# flashlightswitchv02.net
KiCad netlist of a schematic drawn in EAGLE
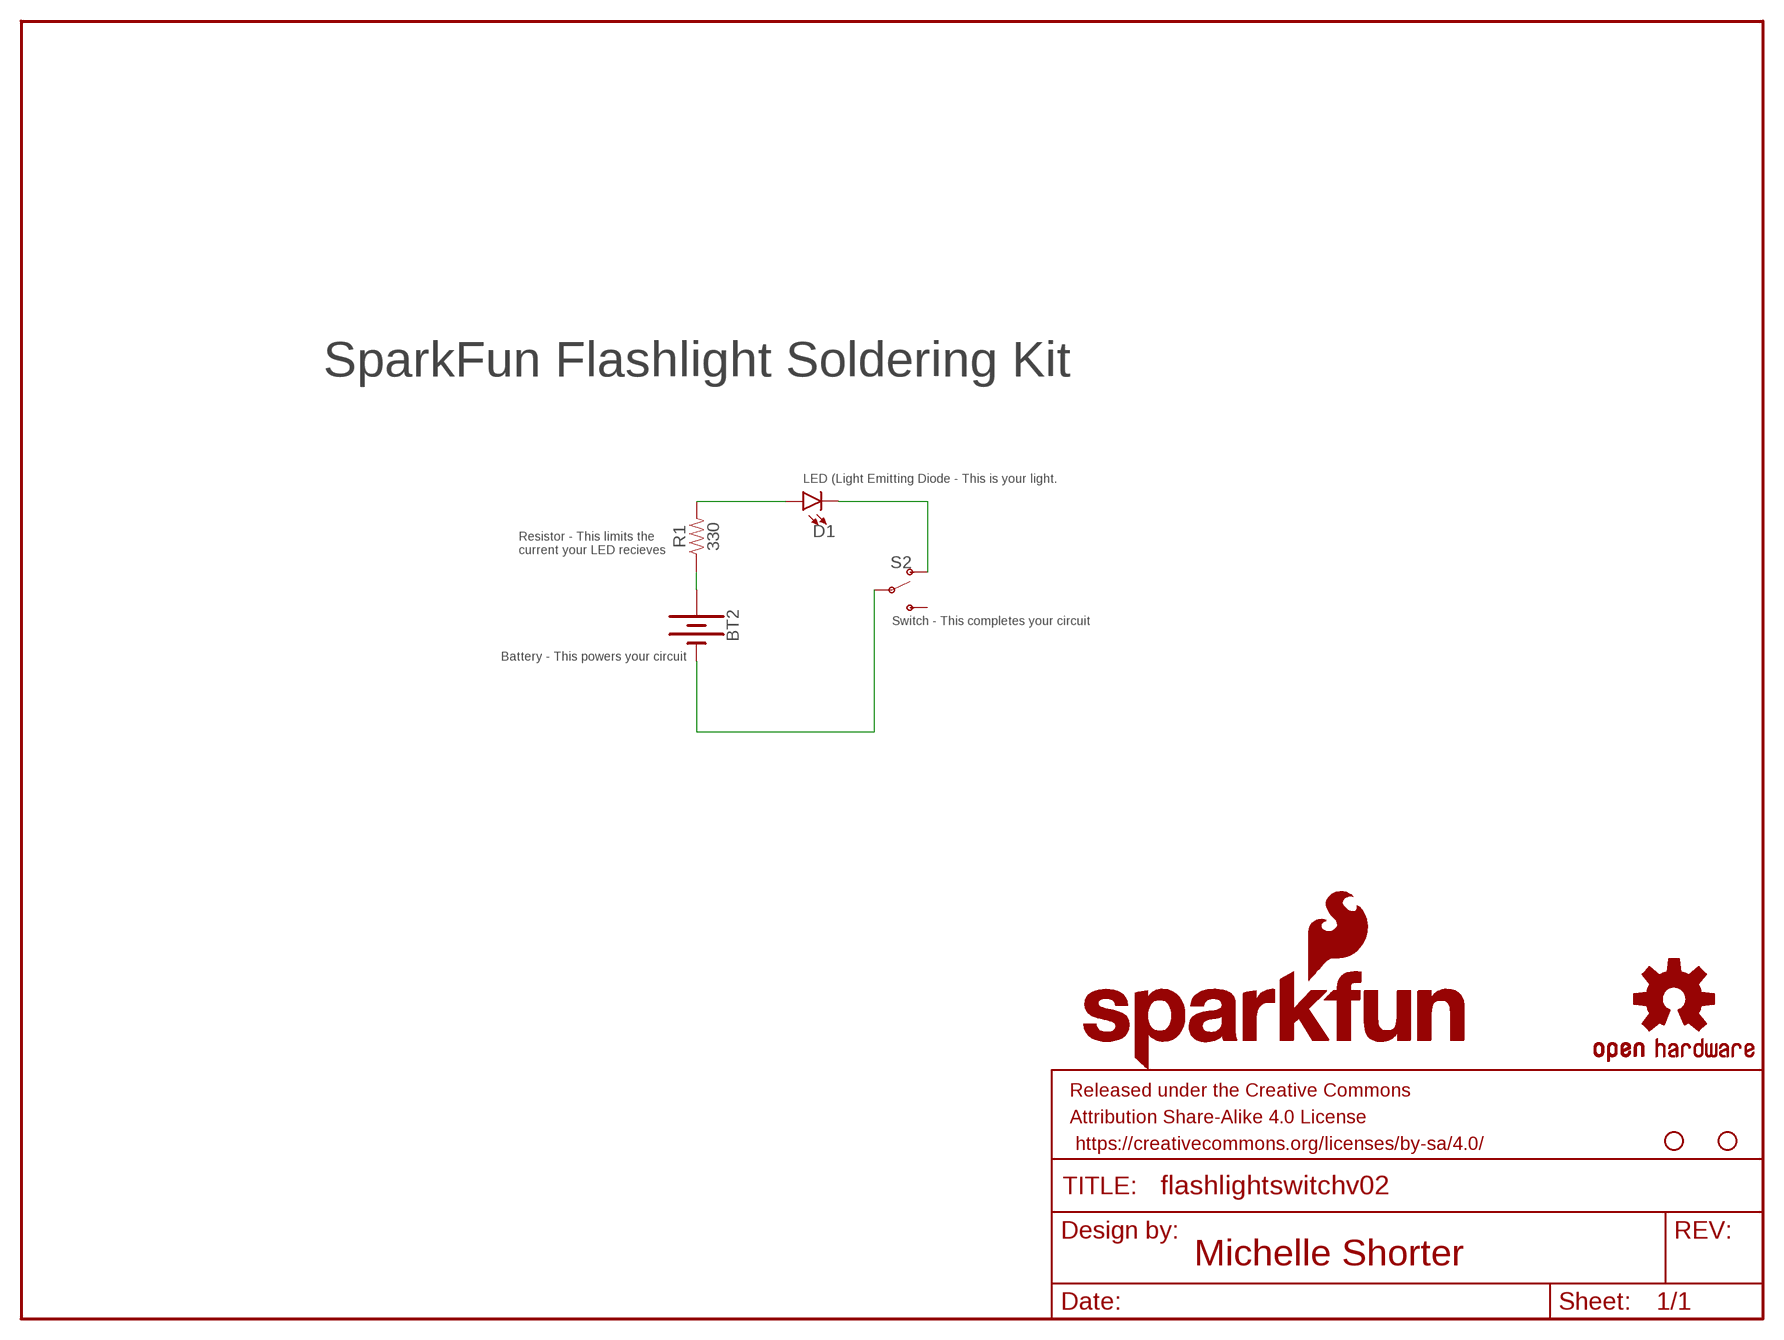
[diagram p0: schematic, sheet 1]

(export (version "E")
  (design (tool "Eeschema 10.0.6"))
  (components
    (comp (ref "BT2")
      (value "BATTERY-20MM_PTH_KIT")
      (footprint "eagle-import:BATTCOM_20MM_PTH_KIT")
      (libsource (lib "eagle-import") (part "BATTERY-20MM_PTH_KIT"))
    )
    (comp (ref "D1")
      (value "LED-5MM-KIT-NO-SILK")
      (footprint "eagle-import:LED_5MM-KIT-NO-SILK")
      (libsource (lib "eagle-import") (part "LED-5MM-KIT-NO-SILK"))
    )
    (comp (ref "FRAME1")
      (value "FRAME-LETTER")
      (footprint "eagle-import:CREATIVE_COMMONS")
      (libsource (lib "eagle-import") (part "FRAME-LETTER"))
    )
    (comp (ref "H1")
      (value "STAND-OFF")
      (footprint "eagle-import:STAND-OFF")
      (libsource (lib "eagle-import") (part "STAND-OFF"))
    )
    (comp (ref "H2")
      (value "STAND-OFF")
      (footprint "eagle-import:STAND-OFF")
      (libsource (lib "eagle-import") (part "STAND-OFF"))
    )
    (comp (ref "LOGO1")
      (value "OSHW-LOGOS")
      (footprint "eagle-import:OSHW-LOGO-S")
      (libsource (lib "eagle-import") (part "OSHW-LOGOS"))
    )
    (comp (ref "LOGO2")
      (value "SFE_LOGO_FLAME.1_INCH")
      (footprint "eagle-import:SFE_LOGO_FLAME_.1")
      (libsource (lib "eagle-import") (part "SFE_LOGO_FLAME.1_INCH"))
    )
    (comp (ref "LOGO3")
      (value "SFE_LOGO_NAME_FLAME.2_INCH")
      (footprint "eagle-import:SFE_LOGO_NAME_FLAME_.2")
      (libsource (lib "eagle-import") (part "SFE_LOGO_NAME_FLAME.2_INCH"))
    )
    (comp (ref "LOGO4")
      (value "SFE_LOGO_NAME.1_INCH")
      (footprint "eagle-import:SFE_LOGO_NAME_.1")
      (libsource (lib "eagle-import") (part "SFE_LOGO_NAME.1_INCH"))
    )
    (comp (ref "R1")
      (value "330")
      (footprint "eagle-import:AXIAL-0.3-KIT")
      (libsource (lib "eagle-import") (part "RESISTORAXIAL-0.3-KIT"))
    )
    (comp (ref "S2")
      (value "SWITCH-SPDT-PTH-11.6X4.0MM-KIT")
      (footprint "eagle-import:SWITCH_SPDT_PTH_11.6X4.0MM_KIT")
      (libsource (lib "eagle-import") (part "SWITCH-SPDT-PTH-11.6X4.0MM-KIT"))
    )
  )
  (nets
    (net (code "1") (name "Net-(BT2-+)") (class "Default")
      (node (ref "BT2") (pin "1") (pinfunction "+_1") (pintype "power_in"))
      (node (ref "R1") (pin "P$1") (pinfunction "1_P$1") (pintype "passive"))
    )
    (net (code "2") (name "Net-(BT2--)") (class "Default")
      (node (ref "BT2") (pin "2") (pinfunction "-_2") (pintype "power_in"))
      (node (ref "S2") (pin "2") (pinfunction "P_2") (pintype "passive"))
    )
    (net (code "3") (name "Net-(D1-C)") (class "Default")
      (node (ref "D1") (pin "K") (pinfunction "C_K") (pintype "passive"))
      (node (ref "S2") (pin "1") (pinfunction "O_1") (pintype "passive"))
    )
    (net (code "4") (name "Net-(R1-2)") (class "Default")
      (node (ref "D1") (pin "A") (pinfunction "A_A") (pintype "passive"))
      (node (ref "R1") (pin "P$2") (pinfunction "2_P$2") (pintype "passive"))
    )
    (net (code "5") (name "unconnected-(S2-S-Pad3)") (class "Default")
      (node (ref "S2") (pin "3") (pinfunction "S_3") (pintype "passive"))
    )
  )
)
